# mosfet.net
KiCad netlist of a schematic drawn in EAGLE
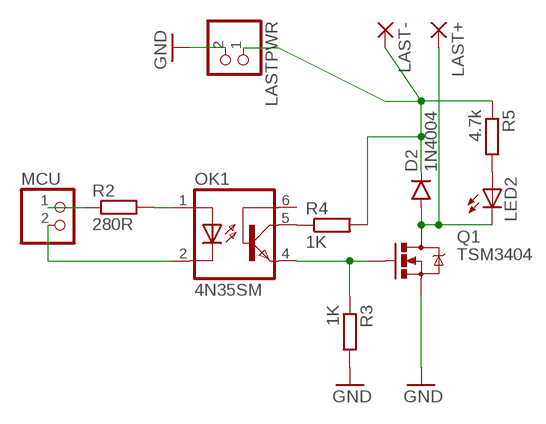
[diagram p0: schematic, sheet 1]

(export (version "E")
  (design (tool "Eeschema 10.0.6"))
  (components
    (comp (ref "D2")
      (value "1N4004")
      (footprint "eagle-import:SOD-123")
      (libsource (lib "eagle-import") (part "DIODESOD123"))
    )
    (comp (ref "LAST+")
      (value "WIREPADSMD2,54-5,08")
      (footprint "eagle-import:SMD2,54-5,08")
      (libsource (lib "eagle-import") (part "WIREPADSMD2,54-5,08"))
    )
    (comp (ref "LAST-")
      (value "WIREPADSMD2,54-5,08")
      (footprint "eagle-import:SMD2,54-5,08")
      (libsource (lib "eagle-import") (part "WIREPADSMD2,54-5,08"))
    )
    (comp (ref "LASTPWR")
      (value "PINHD-1X2")
      (footprint "eagle-import:1X02")
      (libsource (lib "eagle-import") (part "PINHD-1X2"))
    )
    (comp (ref "LED2")
      (value "LEDCHIP-LED0805")
      (footprint "eagle-import:CHIP-LED0805")
      (libsource (lib "eagle-import") (part "LEDCHIP-LED0805"))
    )
    (comp (ref "MCU")
      (value "PINHD-1X2")
      (footprint "eagle-import:1X02")
      (libsource (lib "eagle-import") (part "PINHD-1X2"))
    )
    (comp (ref "OK1")
      (value "4N35SM")
      (footprint "eagle-import:DIL6-SMD")
      (fields (field (name "MF") "FAIRCHILD SEMICONDUCTOR") (field (name "MPN") "4N35S-M"))
      (libsource (lib "eagle-import") (part "4N?MS35"))
    )
    (comp (ref "Q1")
      (value "TSM3404")
      (footprint "eagle-import:SOT23-3")
      (libsource (lib "eagle-import") (part "MOSFET-NCHANNELBSS123LT1G"))
    )
    (comp (ref "R2")
      (value "280R")
      (footprint "eagle-import:R0805")
      (libsource (lib "eagle-import") (part "R-EU_R0805"))
    )
    (comp (ref "R3")
      (value "1K")
      (footprint "eagle-import:R0805")
      (libsource (lib "eagle-import") (part "R-EU_R0805"))
    )
    (comp (ref "R4")
      (value "1K")
      (footprint "eagle-import:R0805")
      (libsource (lib "eagle-import") (part "R-EU_R0805"))
    )
    (comp (ref "R5")
      (value "4.7k")
      (footprint "eagle-import:R0805")
      (libsource (lib "eagle-import") (part "R-EU_R0805"))
    )
  )
  (nets
    (net (code "1") (name "GND") (class "Default")
      (node (ref "LASTPWR") (pin "2") (pinfunction "2_2") (pintype "passive"))
      (node (ref "Q1") (pin "2") (pinfunction "S_2") (pintype "passive"))
      (node (ref "R3") (pin "2") (pinfunction "2_2") (pintype "passive"))
    )
    (net (code "2") (name "Net-(LAST+-P)") (class "Default")
      (node (ref "D2") (pin "A") (pinfunction "A_A") (pintype "passive"))
      (node (ref "LAST+") (pin "1") (pinfunction "P_1") (pintype "passive"))
      (node (ref "LED2") (pin "C") (pinfunction "C_C") (pintype "passive"))
      (node (ref "Q1") (pin "3") (pinfunction "D_3") (pintype "passive"))
    )
    (net (code "3") (name "Net-(LAST--P)") (class "Default")
      (node (ref "D2") (pin "C") (pinfunction "C_C") (pintype "passive"))
      (node (ref "LAST-") (pin "1") (pinfunction "P_1") (pintype "passive"))
      (node (ref "LASTPWR") (pin "1") (pinfunction "1_1") (pintype "passive"))
      (node (ref "R4") (pin "2") (pinfunction "2_2") (pintype "passive"))
      (node (ref "R5") (pin "1") (pinfunction "1_1") (pintype "passive"))
    )
    (net (code "4") (name "Net-(LED2-PadA)") (class "Default")
      (node (ref "LED2") (pin "A") (pinfunction "A_A") (pintype "passive"))
      (node (ref "R5") (pin "2") (pinfunction "2_2") (pintype "passive"))
    )
    (net (code "5") (name "Net-(MCU-Pad1)") (class "Default")
      (node (ref "MCU") (pin "1") (pinfunction "1_1") (pintype "passive"))
      (node (ref "R2") (pin "1") (pinfunction "1_1") (pintype "passive"))
    )
    (net (code "6") (name "Net-(OK1-A)") (class "Default")
      (node (ref "OK1") (pin "1") (pinfunction "A_1") (pintype "passive"))
      (node (ref "R2") (pin "2") (pinfunction "2_2") (pintype "passive"))
    )
    (net (code "7") (name "Net-(OK1-C)") (class "Default")
      (node (ref "MCU") (pin "2") (pinfunction "2_2") (pintype "passive"))
      (node (ref "OK1") (pin "2") (pinfunction "C_2") (pintype "passive"))
    )
    (net (code "8") (name "Net-(OK1-COL)") (class "Default")
      (node (ref "OK1") (pin "5") (pinfunction "COL_5") (pintype "passive"))
      (node (ref "R4") (pin "1") (pinfunction "1_1") (pintype "passive"))
    )
    (net (code "9") (name "Net-(OK1-EMI)") (class "Default")
      (node (ref "OK1") (pin "4") (pinfunction "EMI_4") (pintype "passive"))
      (node (ref "Q1") (pin "1") (pinfunction "G_1") (pintype "passive"))
      (node (ref "R3") (pin "1") (pinfunction "1_1") (pintype "passive"))
    )
    (net (code "10") (name "unconnected-(OK1-BAS-Pad6)") (class "Default")
      (node (ref "OK1") (pin "6") (pinfunction "BAS_6") (pintype "passive"))
    )
  )
)
